# 8051.net
KiCad netlist of a schematic drawn in Altium Designer
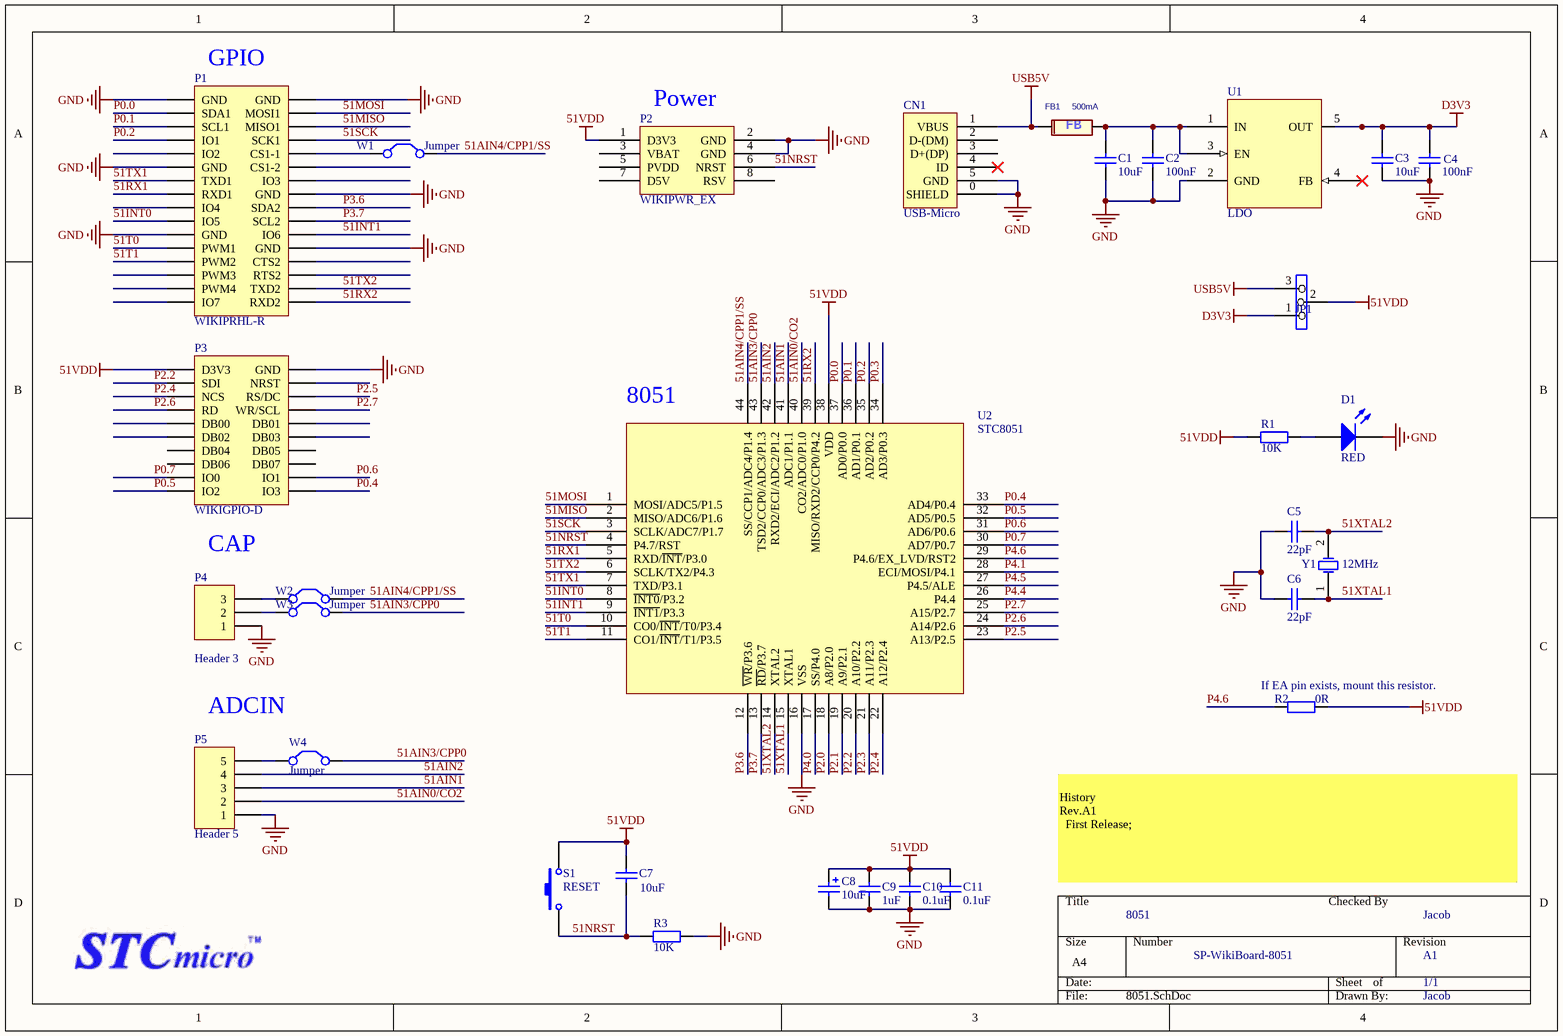
[diagram p0: 8051.SchDoc]

(export (version "E")
  (design (tool "Eeschema 10.0.6"))
  (components
    (comp (ref "C1")
      (value "10uF")
      (footprint "C0805")
      (description "Capacitor")
      (fields (field (name "PUBLISHER") "Altium Limited"))
      (libsource (lib "Miscellaneous Devices") (part "Cap"))
    )
    (comp (ref "C2")
      (value "100nF")
      (footprint "C0603L")
      (description "Capacitor")
      (fields (field (name "PUBLISHER") "Altium Limited"))
      (libsource (lib "Miscellaneous Devices") (part "Cap"))
    )
    (comp (ref "C3")
      (value "10uF")
      (footprint "C0805")
      (description "Capacitor")
      (fields (field (name "PUBLISHER") "Altium Limited"))
      (libsource (lib "Miscellaneous Devices") (part "Cap"))
    )
    (comp (ref "C4")
      (value "100nF")
      (footprint "C0603L")
      (description "Capacitor")
      (fields (field (name "PUBLISHER") "Altium Limited"))
      (libsource (lib "Miscellaneous Devices") (part "Cap"))
    )
    (comp (ref "C5")
      (value "22pF")
      (footprint "C0603L")
      (description "Capacitor")
      (fields (field (name "PUBLISHER") "Altium Limited"))
      (libsource (lib "Miscellaneous Devices") (part "Cap"))
    )
    (comp (ref "C6")
      (value "22pF")
      (footprint "C0603L")
      (description "Capacitor")
      (fields (field (name "PUBLISHER") "Altium Limited"))
      (libsource (lib "Miscellaneous Devices") (part "Cap"))
    )
    (comp (ref "C7")
      (value "10uF")
      (footprint "C0805")
      (description "Capacitor")
      (fields (field (name "PUBLISHER") "Altium Limited"))
      (libsource (lib "Miscellaneous Devices") (part "Cap"))
    )
    (comp (ref "C8")
      (value "10uF")
      (footprint "TAJ-A")
      (description "Polarized Capacitor (Radial)")
      (fields (field (name "PUBLISHER") "Altium Limited"))
      (libsource (lib "Studio") (part "Cap Pol1"))
    )
    (comp (ref "C9")
      (value "1uF")
      (footprint "C0603L")
      (description "Capacitor")
      (fields (field (name "PUBLISHER") "Altium Limited"))
      (libsource (lib "Miscellaneous Devices") (part "Cap"))
    )
    (comp (ref "C10")
      (value "0.1uF")
      (footprint "C0603L")
      (description "Capacitor")
      (fields (field (name "PUBLISHER") "Altium Limited"))
      (libsource (lib "Miscellaneous Devices") (part "=Value"))
    )
    (comp (ref "C11")
      (value "0.1uF")
      (footprint "C0603L")
      (description "Capacitor")
      (fields (field (name "PUBLISHER") "Altium Limited"))
      (libsource (lib "Miscellaneous Devices") (part "Cap"))
    )
    (comp (ref "CN1")
      (value "USB-Micro")
      (footprint "USB_MICRO_5S_B")
      (libsource (lib "Connector") (part "USB-Micro"))
    )
    (comp (ref "D1")
      (value "RED")
      (footprint "SMT_LED_0603")
      (description "Typical INFRARED GaAs LED")
      (fields (field (name "PUBLISHER") "Altium Limited"))
      (libsource (lib "Miscellaneous Devices") (part "LED0"))
    )
    (comp (ref "FB1")
      (value "500mA")
      (footprint "R1206")
      (description "Ferrite Beads Inductors Impedance:120Ω±25% Rated Current:1500mA DC Resistance:0.095Ω")
      (fields
        (field (name "MANUFACTURER") "muRata")
        (field (name "MANUFACTURER PART NUMBER") "BLM15EG121SN1")
      )
      (libsource (lib "Mylib") (part "FB"))
    )
    (comp (ref "JP1") (value "JP3") (footprint "SIP3") (libsource (lib "Connector") (part "JP3")))
    (comp (ref "P1")
      (value "WIKIPRHL-R")
      (footprint "WIKIPRHL-R")
      (description "Header, 16-Pin, Dual row")
      (fields (field (name "PUBLISHER") "Altium Limited"))
      (libsource (lib "Connector") (part "WIKIPRHL-R"))
    )
    (comp (ref "P2")
      (value "WIKIPWR_EX")
      (footprint "WIKIPWR_EX")
      (description "PWR HDR")
      (libsource (lib "Connector") (part "WIKIPWR_EX"))
    )
    (comp (ref "P3")
      (value "WIKIGPIO-D")
      (footprint "WIKIGPIO-D")
      (description "Header, 9-Pin, Dual row")
      (fields (field (name "PUBLISHER") "Altium Limited"))
      (libsource (lib "Connector") (part "WIKIGPIO-D"))
    )
    (comp (ref "P4")
      (value "Header 3")
      (footprint "HDR1X3/2.54mm")
      (description "Header, 3-Pin")
      (fields (field (name "PUBLISHER") "Altium Limited"))
      (libsource (lib "Miscellaneous Connectors") (part "Header 3"))
    )
    (comp (ref "P5")
      (value "Header 5")
      (footprint "HDR1X5/2.54MM")
      (description "Header, 5-Pin")
      (fields (field (name "PUBLISHER") "Altium Limited"))
      (libsource (lib "Miscellaneous Connectors") (part "Header 5"))
    )
    (comp (ref "R1")
      (value "10K")
      (footprint "R0603")
      (description "Resistor")
      (fields (field (name "PUBLISHER") "Altium Limited"))
      (libsource (lib "") (part "Res2_1"))
    )
    (comp (ref "R2")
      (value "0R")
      (footprint "R0603")
      (description "Resistor")
      (fields (field (name "PUBLISHER") "Altium Limited"))
      (libsource (lib "Miscellaneous Devices") (part "Res2"))
    )
    (comp (ref "R3")
      (value "10K")
      (footprint "R0603")
      (description "Resistor")
      (fields (field (name "PUBLISHER") "Altium Limited"))
      (libsource (lib "") (part "Res2_1"))
    )
    (comp (ref "S1")
      (value "RESET")
      (footprint "KEY-2x4-SMD")
      (description "Switch")
      (fields (field (name "PUBLISHER") "Altium Limited"))
      (libsource (lib "Miscellaneous Devices") (part "SW-PB"))
    )
    (comp (ref "U1")
      (value "LDO")
      (footprint "SOT23-5")
      (description "General LDO SOT23-5")
      (libsource (lib "Power") (part "LDO-SOT23-5"))
    )
    (comp (ref "U2")
      (value "STC8051")
      (footprint "TQFP44")
      (description "STC12LE5A")
      (libsource (lib "Lunio") (part "STC12LE5A"))
    )
    (comp (ref "W1")
      (value "Jumper")
      (footprint "Solderbridge")
      (description "Jumper Wire")
      (fields (field (name "PUBLISHER") "Altium Limited"))
      (libsource (lib "Miscellaneous Devices") (part "Jumper"))
    )
    (comp (ref "W2")
      (value "Jumper")
      (footprint "Solderbridge")
      (description "Jumper Wire")
      (fields (field (name "PUBLISHER") "Altium Limited"))
      (libsource (lib "Miscellaneous Devices") (part "Jumper"))
    )
    (comp (ref "W3")
      (value "Jumper")
      (footprint "Solderbridge")
      (description "Jumper Wire")
      (fields (field (name "PUBLISHER") "Altium Limited"))
      (libsource (lib "Miscellaneous Devices") (part "Jumper"))
    )
    (comp (ref "W4")
      (value "Jumper")
      (footprint "Solderbridge")
      (description "Jumper Wire")
      (fields (field (name "PUBLISHER") "Altium Limited"))
      (libsource (lib "Miscellaneous Devices") (part "Jumper"))
    )
    (comp (ref "Y1")
      (value "12MHz")
      (footprint "XTAL0602")
      (description "Crystal Oscillator")
      (fields (field (name "PUBLISHER") "Altium Limited"))
      (libsource (lib "Miscellaneous Devices") (part "XTAL"))
    )
  )
  (nets
    (net (code "1") (name "/51AIN0{slash}CO2") (class "Default")
      (node (ref "P5") (pin "2") (pinfunction "2_2") (pintype "passive"))
      (node (ref "U2") (pin "40") (pinfunction "CO2/ADC0/P1.0_40") (pintype "passive"))
    )
    (net (code "2") (name "/51AIN1") (class "Default")
      (node (ref "P5") (pin "3") (pinfunction "3_3") (pintype "passive"))
      (node (ref "U2") (pin "41") (pinfunction "ADC1/P1.1_41") (pintype "passive"))
    )
    (net (code "3") (name "/51AIN2") (class "Default")
      (node (ref "P5") (pin "4") (pinfunction "4_4") (pintype "passive"))
      (node (ref "U2") (pin "42") (pinfunction "RXD2/ECI/ADC2/P1.2_42") (pintype "passive"))
    )
    (net (code "4") (name "/51AIN3{slash}CPP0") (class "Default")
      (node (ref "U2") (pin "43") (pinfunction "TSD2/CCP0/ADC3/P1.3_43") (pintype "passive"))
      (node (ref "W3") (pin "2") (pinfunction "C2_2") (pintype "passive"))
      (node (ref "W4") (pin "2") (pinfunction "C2_2") (pintype "passive"))
    )
    (net (code "5") (name "/51AIN4{slash}CPP1{slash}SS") (class "Default")
      (node (ref "U2") (pin "44") (pinfunction "SS/CCP1/ADC4/P1.4_44") (pintype "passive"))
      (node (ref "W1") (pin "1") (pinfunction "C1_1") (pintype "passive"))
      (node (ref "W2") (pin "2") (pinfunction "C2_2") (pintype "passive"))
    )
    (net (code "6") (name "/51INT0") (class "Default")
      (node (ref "P1") (pin "19") (pinfunction "IO5_19") (pintype "passive"))
      (node (ref "U2") (pin "8") (pinfunction "~{INT0}/P3.2_8") (pintype "passive"))
    )
    (net (code "7") (name "/51INT1") (class "Default")
      (node (ref "P1") (pin "22") (pinfunction "IO6_22") (pintype "passive"))
      (node (ref "U2") (pin "9") (pinfunction "~{INT1}/P3.3_9") (pintype "passive"))
    )
    (net (code "8") (name "/51MISO") (class "Default")
      (node (ref "P1") (pin "6") (pinfunction "MISO1_6") (pintype "passive"))
      (node (ref "U2") (pin "2") (pinfunction "MISO/ADC6/P1.6_2") (pintype "passive"))
    )
    (net (code "9") (name "/51MOSI") (class "Default")
      (node (ref "P1") (pin "4") (pinfunction "MOSI1_4") (pintype "passive"))
      (node (ref "U2") (pin "1") (pinfunction "MOSI/ADC5/P1.5_1") (pintype "passive"))
    )
    (net (code "10") (name "/51NRST") (class "Default")
      (node (ref "C7") (pin "1") (pinfunction "1_1") (pintype "passive"))
      (node (ref "P2") (pin "6") (pinfunction "NRST_6") (pintype "passive"))
      (node (ref "R3") (pin "2") (pinfunction "2_2") (pintype "passive"))
      (node (ref "S1") (pin "1") (pinfunction "1_1") (pintype "passive"))
      (node (ref "U2") (pin "4") (pinfunction "P4.7/RST_4") (pintype "passive"))
    )
    (net (code "11") (name "/51RX1") (class "Default")
      (node (ref "P1") (pin "15") (pinfunction "RXD1_15") (pintype "passive"))
      (node (ref "U2") (pin "5") (pinfunction "RXD/~{INT}/P3.0_5") (pintype "passive"))
    )
    (net (code "12") (name "/51RX2") (class "Default")
      (node (ref "P1") (pin "32") (pinfunction "RXD2_32") (pintype "passive"))
      (node (ref "U2") (pin "39") (pinfunction "MISO/RXD2/CCP0/P4.2_39") (pintype "passive"))
    )
    (net (code "13") (name "/51SCK") (class "Default")
      (node (ref "P1") (pin "8") (pinfunction "SCK1_8") (pintype "passive"))
      (node (ref "U2") (pin "3") (pinfunction "SCLK/ADC7/P1.7_3") (pintype "passive"))
    )
    (net (code "14") (name "/51T0") (class "Default")
      (node (ref "P1") (pin "23") (pinfunction "PWM1_23") (pintype "passive"))
      (node (ref "U2") (pin "10") (pinfunction "CO0/~{INT}/T0/P3.4_10") (pintype "passive"))
    )
    (net (code "15") (name "/51T1") (class "Default")
      (node (ref "P1") (pin "25") (pinfunction "PWM2_25") (pintype "passive"))
      (node (ref "U2") (pin "11") (pinfunction "CO1/~{INT}/T1/P3.5_11") (pintype "passive"))
    )
    (net (code "16") (name "/51TX1") (class "Default")
      (node (ref "P1") (pin "13") (pinfunction "TXD1_13") (pintype "passive"))
      (node (ref "U2") (pin "7") (pinfunction "TXD/P3.1_7") (pintype "passive"))
    )
    (net (code "17") (name "/51TX2") (class "Default")
      (node (ref "P1") (pin "30") (pinfunction "TXD2_30") (pintype "passive"))
      (node (ref "U2") (pin "6") (pinfunction "SCLK/TX2/P4.3_6") (pintype "passive"))
    )
    (net (code "18") (name "/51XTAL1") (class "Default")
      (node (ref "C6") (pin "2") (pinfunction "2_2") (pintype "passive"))
      (node (ref "U2") (pin "15") (pinfunction "XTAL1_15") (pintype "passive"))
      (node (ref "Y1") (pin "1") (pinfunction "OSC1_1") (pintype "passive"))
    )
    (net (code "19") (name "/51XTAL2") (class "Default")
      (node (ref "C5") (pin "2") (pinfunction "2_2") (pintype "passive"))
      (node (ref "U2") (pin "14") (pinfunction "XTAL2_14") (pintype "passive"))
      (node (ref "Y1") (pin "2") (pinfunction "OSC2_2") (pintype "passive"))
    )
    (net (code "20") (name "/P0.0") (class "Default")
      (node (ref "P1") (pin "3") (pinfunction "SDA1_3") (pintype "passive"))
      (node (ref "U2") (pin "37") (pinfunction "AD0/P0.0_37") (pintype "passive"))
    )
    (net (code "21") (name "/P0.1") (class "Default")
      (node (ref "P1") (pin "5") (pinfunction "SCL1_5") (pintype "passive"))
      (node (ref "U2") (pin "36") (pinfunction "AD1/P0.1_36") (pintype "passive"))
    )
    (net (code "22") (name "/P0.2") (class "Default")
      (node (ref "P1") (pin "7") (pinfunction "IO1_7") (pintype "passive"))
      (node (ref "U2") (pin "35") (pinfunction "AD2/P0.2_35") (pintype "passive"))
    )
    (net (code "23") (name "/P0.3") (class "Default")
      (node (ref "U2") (pin "34") (pinfunction "AD3/P0.3_34") (pintype "passive"))
    )
    (net (code "24") (name "/P0.4") (class "Default")
      (node (ref "P3") (pin "20") (pinfunction "IO3_20") (pintype "passive"))
      (node (ref "U2") (pin "33") (pinfunction "AD4/P0.4_33") (pintype "passive"))
    )
    (net (code "25") (name "/P0.5") (class "Default")
      (node (ref "P3") (pin "19") (pinfunction "IO2_19") (pintype "passive"))
      (node (ref "U2") (pin "32") (pinfunction "AD5/P0.5_32") (pintype "passive"))
    )
    (net (code "26") (name "/P0.6") (class "Default")
      (node (ref "P3") (pin "18") (pinfunction "IO1_18") (pintype "passive"))
      (node (ref "U2") (pin "31") (pinfunction "AD6/P0.6_31") (pintype "passive"))
    )
    (net (code "27") (name "/P0.7") (class "Default")
      (node (ref "P3") (pin "17") (pinfunction "IO0_17") (pintype "passive"))
      (node (ref "U2") (pin "30") (pinfunction "AD7/P0.7_30") (pintype "passive"))
    )
    (net (code "28") (name "/P2.0") (class "Default")
      (node (ref "U2") (pin "18") (pinfunction "A8/P2.0_18") (pintype "passive"))
    )
    (net (code "29") (name "/P2.1") (class "Default")
      (node (ref "U2") (pin "19") (pinfunction "A9/P2.1_19") (pintype "passive"))
    )
    (net (code "30") (name "/P2.2") (class "Default")
      (node (ref "P3") (pin "3") (pinfunction "SDI_3") (pintype "passive"))
      (node (ref "U2") (pin "20") (pinfunction "A10/P2.2_20") (pintype "passive"))
    )
    (net (code "31") (name "/P2.3") (class "Default")
      (node (ref "U2") (pin "21") (pinfunction "A11/P2.3_21") (pintype "passive"))
    )
    (net (code "32") (name "/P2.4") (class "Default")
      (node (ref "P3") (pin "5") (pinfunction "NCS_5") (pintype "passive"))
      (node (ref "U2") (pin "22") (pinfunction "A12/P2.4_22") (pintype "passive"))
    )
    (net (code "33") (name "/P2.5") (class "Default")
      (node (ref "P3") (pin "6") (pinfunction "RS/DC_6") (pintype "passive"))
      (node (ref "U2") (pin "23") (pinfunction "A13/P2.5_23") (pintype "passive"))
    )
    (net (code "34") (name "/P2.6") (class "Default")
      (node (ref "P3") (pin "7") (pinfunction "RD_7") (pintype "passive"))
      (node (ref "U2") (pin "24") (pinfunction "A14/P2.6_24") (pintype "passive"))
    )
    (net (code "35") (name "/P2.7") (class "Default")
      (node (ref "P3") (pin "8") (pinfunction "WR/SCL_8") (pintype "passive"))
      (node (ref "U2") (pin "25") (pinfunction "A15/P2.7_25") (pintype "passive"))
    )
    (net (code "36") (name "/P3.6") (class "Default")
      (node (ref "P1") (pin "18") (pinfunction "SDA2_18") (pintype "passive"))
      (node (ref "U2") (pin "12") (pinfunction "~{WR}/P3.6_12") (pintype "passive"))
    )
    (net (code "37") (name "/P3.7") (class "Default")
      (node (ref "P1") (pin "20") (pinfunction "SCL2_20") (pintype "passive"))
      (node (ref "U2") (pin "13") (pinfunction "~{RD}/P3.7_13") (pintype "passive"))
    )
    (net (code "38") (name "/P4.0") (class "Default")
      (node (ref "U2") (pin "17") (pinfunction "SS/P4.0_17") (pintype "passive"))
    )
    (net (code "39") (name "/P4.1") (class "Default")
      (node (ref "U2") (pin "28") (pinfunction "ECI/MOSI/P4.1_28") (pintype "passive"))
    )
    (net (code "40") (name "/P4.4") (class "Default")
      (node (ref "U2") (pin "26") (pinfunction "P4.4_26") (pintype "passive"))
    )
    (net (code "41") (name "/P4.5") (class "Default")
      (node (ref "U2") (pin "27") (pinfunction "P4.5/ALE_27") (pintype "passive"))
    )
    (net (code "42") (name "/P4.6") (class "Default")
      (node (ref "R2") (pin "1") (pinfunction "1_1") (pintype "passive"))
      (node (ref "U2") (pin "29") (pinfunction "P4.6/EX_LVD/RST2_29") (pintype "passive"))
    )
    (net (code "43") (name "51VDD") (class "Default")
      (node (ref "C10") (pin "2") (pinfunction "2_2") (pintype "passive"))
      (node (ref "C11") (pin "2") (pinfunction "2_2") (pintype "passive"))
      (node (ref "C7") (pin "2") (pinfunction "2_2") (pintype "passive"))
      (node (ref "C8") (pin "1") (pinfunction "1_1") (pintype "passive"))
      (node (ref "C9") (pin "2") (pinfunction "2_2") (pintype "passive"))
      (node (ref "JP1") (pin "2") (pintype "passive"))
      (node (ref "P2") (pin "1") (pinfunction "D3V3_1") (pintype "passive"))
      (node (ref "P3") (pin "1") (pinfunction "D3V3_1") (pintype "passive"))
      (node (ref "R1") (pin "2") (pinfunction "2_2") (pintype "passive"))
      (node (ref "R2") (pin "2") (pinfunction "2_2") (pintype "passive"))
      (node (ref "S1") (pin "2") (pinfunction "2_2") (pintype "passive"))
      (node (ref "U2") (pin "38") (pinfunction "VDD_38") (pintype "passive"))
    )
    (net (code "44") (name "D3V3") (class "Default")
      (node (ref "C3") (pin "1") (pinfunction "1_1") (pintype "passive"))
      (node (ref "C4") (pin "1") (pinfunction "1_1") (pintype "passive"))
      (node (ref "JP1") (pin "1") (pintype "passive"))
      (node (ref "U1") (pin "5") (pinfunction "OUT_5") (pintype "power_in"))
    )
    (net (code "45") (name "GND") (class "Default")
      (node (ref "C1") (pin "2") (pinfunction "2_2") (pintype "passive"))
      (node (ref "C10") (pin "1") (pinfunction "1_1") (pintype "passive"))
      (node (ref "C11") (pin "1") (pinfunction "1_1") (pintype "passive"))
      (node (ref "C2") (pin "2") (pinfunction "2_2") (pintype "passive"))
      (node (ref "C3") (pin "2") (pinfunction "2_2") (pintype "passive"))
      (node (ref "C4") (pin "2") (pinfunction "2_2") (pintype "passive"))
      (node (ref "C5") (pin "1") (pinfunction "1_1") (pintype "passive"))
      (node (ref "C6") (pin "1") (pinfunction "1_1") (pintype "passive"))
      (node (ref "C8") (pin "2") (pinfunction "2_2") (pintype "passive"))
      (node (ref "C9") (pin "1") (pinfunction "1_1") (pintype "passive"))
      (node (ref "CN1") (pin "0") (pinfunction "SHIELD_0") (pintype "passive"))
      (node (ref "CN1") (pin "5") (pinfunction "GND_5") (pintype "passive"))
      (node (ref "D1") (pin "2") (pinfunction "K_2") (pintype "passive"))
      (node (ref "P1") (pin "1") (pinfunction "GND_1") (pintype "passive"))
      (node (ref "P1") (pin "11") (pinfunction "GND_11") (pintype "passive"))
      (node (ref "P1") (pin "16") (pinfunction "GND_16") (pintype "passive"))
      (node (ref "P1") (pin "2") (pinfunction "GND_2") (pintype "passive"))
      (node (ref "P1") (pin "21") (pinfunction "GND_21") (pintype "passive"))
      (node (ref "P1") (pin "24") (pinfunction "GND_24") (pintype "passive"))
      (node (ref "P2") (pin "2") (pinfunction "GND_2") (pintype "passive"))
      (node (ref "P2") (pin "4") (pinfunction "GND_4") (pintype "passive"))
      (node (ref "P3") (pin "2") (pinfunction "GND_2") (pintype "passive"))
      (node (ref "P4") (pin "1") (pinfunction "1_1") (pintype "passive"))
      (node (ref "P5") (pin "1") (pinfunction "1_1") (pintype "passive"))
      (node (ref "R3") (pin "1") (pinfunction "1_1") (pintype "passive"))
      (node (ref "U1") (pin "2") (pinfunction "GND_2") (pintype "power_in"))
      (node (ref "U2") (pin "16") (pinfunction "VSS_16") (pintype "passive"))
    )
    (net (code "46") (name "Net-(D1-A)") (class "Default")
      (node (ref "D1") (pin "1") (pinfunction "A_1") (pintype "passive"))
      (node (ref "R1") (pin "1") (pinfunction "1_1") (pintype "passive"))
    )
    (net (code "47") (name "Net-(P1-CS1-1)") (class "Default")
      (node (ref "P1") (pin "10") (pinfunction "CS1-1_10") (pintype "passive"))
      (node (ref "W1") (pin "2") (pinfunction "C2_2") (pintype "passive"))
    )
    (net (code "48") (name "Net-(U1-EN)") (class "Default")
      (node (ref "C1") (pin "1") (pinfunction "1_1") (pintype "passive"))
      (node (ref "C2") (pin "1") (pinfunction "1_1") (pintype "passive"))
      (node (ref "FB1") (pin "2") (pinfunction "2_2") (pintype "passive"))
      (node (ref "U1") (pin "1") (pinfunction "IN_1") (pintype "power_in"))
      (node (ref "U1") (pin "3") (pinfunction "EN_3") (pintype "input"))
    )
    (net (code "49") (name "Net-(W2-C1)") (class "Default")
      (node (ref "P4") (pin "3") (pinfunction "3_3") (pintype "passive"))
      (node (ref "W2") (pin "1") (pinfunction "C1_1") (pintype "passive"))
    )
    (net (code "50") (name "Net-(W3-C1)") (class "Default")
      (node (ref "P4") (pin "2") (pinfunction "2_2") (pintype "passive"))
      (node (ref "W3") (pin "1") (pinfunction "C1_1") (pintype "passive"))
    )
    (net (code "51") (name "Net-(W4-C1)") (class "Default")
      (node (ref "P5") (pin "5") (pinfunction "5_5") (pintype "passive"))
      (node (ref "W4") (pin "1") (pinfunction "C1_1") (pintype "passive"))
    )
    (net (code "52") (name "USB5V") (class "Default")
      (node (ref "CN1") (pin "1") (pinfunction "VBUS_1") (pintype "passive"))
      (node (ref "FB1") (pin "1") (pinfunction "1_1") (pintype "passive"))
      (node (ref "JP1") (pin "3") (pintype "passive"))
    )
    (net (code "53") (name "unconnected-(CN1-D+(DP)-Pad3)") (class "Default")
      (node (ref "CN1") (pin "3") (pinfunction "D+(DP)_3") (pintype "passive"))
    )
    (net (code "54") (name "unconnected-(CN1-D-(DM)-Pad2)") (class "Default")
      (node (ref "CN1") (pin "2") (pinfunction "D-(DM)_2") (pintype "passive"))
    )
    (net (code "55") (name "unconnected-(CN1-ID-Pad4)") (class "Default")
      (node (ref "CN1") (pin "4") (pinfunction "ID_4") (pintype "passive+no_connect"))
    )
    (net (code "56") (name "unconnected-(P1-CS1-2-Pad12)") (class "Default")
      (node (ref "P1") (pin "12") (pinfunction "CS1-2_12") (pintype "passive"))
    )
    (net (code "57") (name "unconnected-(P1-CTS2-Pad26)") (class "Default")
      (node (ref "P1") (pin "26") (pinfunction "CTS2_26") (pintype "passive"))
    )
    (net (code "58") (name "unconnected-(P1-IO2-Pad9)") (class "Default")
      (node (ref "P1") (pin "9") (pinfunction "IO2_9") (pintype "passive"))
    )
    (net (code "59") (name "unconnected-(P1-IO3-Pad14)") (class "Default")
      (node (ref "P1") (pin "14") (pinfunction "IO3_14") (pintype "passive"))
    )
    (net (code "60") (name "unconnected-(P1-IO4-Pad17)") (class "Default")
      (node (ref "P1") (pin "17") (pinfunction "IO4_17") (pintype "passive"))
    )
    (net (code "61") (name "unconnected-(P1-IO7-Pad31)") (class "Default")
      (node (ref "P1") (pin "31") (pinfunction "IO7_31") (pintype "passive"))
    )
    (net (code "62") (name "unconnected-(P1-PWM3-Pad27)") (class "Default")
      (node (ref "P1") (pin "27") (pinfunction "PWM3_27") (pintype "passive"))
    )
    (net (code "63") (name "unconnected-(P1-PWM4-Pad29)") (class "Default")
      (node (ref "P1") (pin "29") (pinfunction "PWM4_29") (pintype "passive"))
    )
    (net (code "64") (name "unconnected-(P1-RTS2-Pad28)") (class "Default")
      (node (ref "P1") (pin "28") (pinfunction "RTS2_28") (pintype "passive"))
    )
    (net (code "65") (name "unconnected-(P2-D5V-Pad7)") (class "Default")
      (node (ref "P2") (pin "7") (pinfunction "D5V_7") (pintype "passive"))
    )
    (net (code "66") (name "unconnected-(P2-PVDD-Pad5)") (class "Default")
      (node (ref "P2") (pin "5") (pinfunction "PVDD_5") (pintype "passive"))
    )
    (net (code "67") (name "unconnected-(P2-RSV-Pad8)") (class "Default")
      (node (ref "P2") (pin "8") (pinfunction "RSV_8") (pintype "passive"))
    )
    (net (code "68") (name "unconnected-(P2-VBAT-Pad3)") (class "Default")
      (node (ref "P2") (pin "3") (pinfunction "VBAT_3") (pintype "passive"))
    )
    (net (code "69") (name "unconnected-(P3-DB00-Pad9)") (class "Default")
      (node (ref "P3") (pin "9") (pinfunction "DB00_9") (pintype "passive"))
    )
    (net (code "70") (name "unconnected-(P3-DB01-Pad10)") (class "Default")
      (node (ref "P3") (pin "10") (pinfunction "DB01_10") (pintype "passive"))
    )
    (net (code "71") (name "unconnected-(P3-DB02-Pad11)") (class "Default")
      (node (ref "P3") (pin "11") (pinfunction "DB02_11") (pintype "passive"))
    )
    (net (code "72") (name "unconnected-(P3-DB03-Pad12)") (class "Default")
      (node (ref "P3") (pin "12") (pinfunction "DB03_12") (pintype "passive"))
    )
    (net (code "73") (name "unconnected-(P3-DB04-Pad13)") (class "Default")
      (node (ref "P3") (pin "13") (pinfunction "DB04_13") (pintype "passive"))
    )
    (net (code "74") (name "unconnected-(P3-DB05-Pad14)") (class "Default")
      (node (ref "P3") (pin "14") (pinfunction "DB05_14") (pintype "passive"))
    )
    (net (code "75") (name "unconnected-(P3-DB06-Pad15)") (class "Default")
      (node (ref "P3") (pin "15") (pinfunction "DB06_15") (pintype "passive"))
    )
    (net (code "76") (name "unconnected-(P3-DB07-Pad16)") (class "Default")
      (node (ref "P3") (pin "16") (pinfunction "DB07_16") (pintype "passive"))
    )
    (net (code "77") (name "unconnected-(P3-NRST-Pad4)") (class "Default")
      (node (ref "P3") (pin "4") (pinfunction "NRST_4") (pintype "passive"))
    )
    (net (code "78") (name "unconnected-(U1-FB-Pad4)") (class "Default")
      (node (ref "U1") (pin "4") (pinfunction "FB_4") (pintype "input+no_connect"))
    )
  )
)
